# digi_5V.net
KiCad netlist of a schematic drawn in Altium Designer
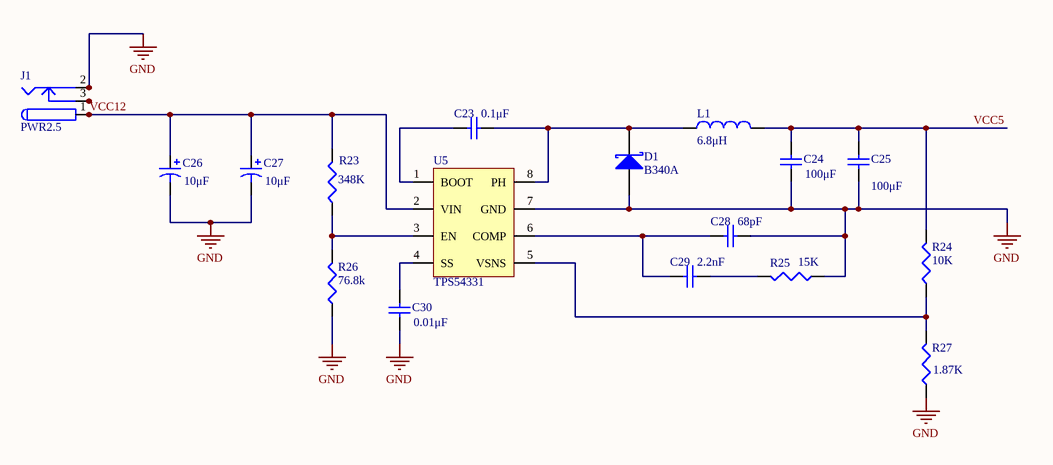
[diagram p0: digi_5V.SchDoc]

(export (version "E")
  (design (tool "Eeschema 10.0.6"))
  (components
    (comp (ref "C23")
      (value "0.1μF")
      (footprint "1608[0603]")
      (description "Capacitor (Semiconductor SIM Model)")
      (fields (field (name "Comment") "Cap Semi") (field (name "PUBLISHER") "Altium Limited"))
      (libsource (lib "Miscellaneous Devices") (part "Cap Semi"))
    )
    (comp (ref "C24")
      (value "100μF")
      (footprint "1608[0603]")
      (description "Capacitor (Semiconductor SIM Model)")
      (fields (field (name "Comment") "Cap Semi") (field (name "PUBLISHER") "Altium Limited"))
      (libsource (lib "Miscellaneous Devices") (part "Cap Semi"))
    )
    (comp (ref "C25")
      (value "100μF")
      (footprint "1608[0603]")
      (description "Capacitor (Semiconductor SIM Model)")
      (fields (field (name "Comment") "Cap Semi") (field (name "PUBLISHER") "Altium Limited"))
      (libsource (lib "Miscellaneous Devices") (part "Cap Semi"))
    )
    (comp (ref "C26")
      (value "10μF")
      (footprint "C0805")
      (description "Polarized Capacitor (Surface Mount)")
      (fields (field (name "Comment") "Cap Pol3") (field (name "PUBLISHER") "Altium Limited"))
      (libsource (lib "Miscellaneous Devices") (part "Cap Pol3"))
    )
    (comp (ref "C27")
      (value "10μF")
      (footprint "C0805")
      (description "Polarized Capacitor (Surface Mount)")
      (fields (field (name "Comment") "Cap Pol3") (field (name "PUBLISHER") "Altium Limited"))
      (libsource (lib "Miscellaneous Devices") (part "Cap Pol3"))
    )
    (comp (ref "C28")
      (value "68pF")
      (footprint "1608[0603]")
      (description "Capacitor (Semiconductor SIM Model)")
      (fields (field (name "Comment") "Cap Semi") (field (name "PUBLISHER") "Altium Limited"))
      (libsource (lib "Miscellaneous Devices") (part "Cap Semi"))
    )
    (comp (ref "C29")
      (value "2.2nF")
      (footprint "1608[0603]")
      (description "Capacitor (Semiconductor SIM Model)")
      (fields (field (name "Comment") "Cap Semi") (field (name "PUBLISHER") "Altium Limited"))
      (libsource (lib "Miscellaneous Devices") (part "Cap Semi"))
    )
    (comp (ref "C30")
      (value "0.01μF")
      (footprint "1608[0603]")
      (description "Capacitor (Semiconductor SIM Model)")
      (fields (field (name "Comment") "Cap Semi") (field (name "PUBLISHER") "Altium Limited"))
      (libsource (lib "Miscellaneous Devices") (part "Cap Semi"))
    )
    (comp (ref "D1")
      (value "B340A")
      (footprint "LED0603")
      (description "Schottky Diode")
      (fields (field (name "PUBLISHER") "Altium Limited"))
      (libsource (lib "Miscellaneous Devices") (part "D Schottky"))
    )
    (comp (ref "J1")
      (value "PWR2.5")
      (footprint "KLD-0202")
      (description "Low Voltage Power Supply Connector")
      (fields (field (name "PUBLISHER") "Altium Limited"))
      (libsource (lib "Miscellaneous Connectors") (part "PWR2.5"))
    )
    (comp (ref "L1")
      (value "6.8μH")
      (footprint "LC Inductor 127")
      (description "Inductor")
      (fields (field (name "PUBLISHER") "Altium Limited"))
      (libsource (lib "Miscellaneous Devices") (part "Inductor"))
    )
    (comp (ref "R23")
      (value "348K")
      (footprint "J1-0603")
      (description "Resistor")
      (fields (field (name "Comment") "Res3") (field (name "PUBLISHER") "Altium Limited"))
      (libsource (lib "Miscellaneous Devices") (part "Res3"))
    )
    (comp (ref "R24")
      (value "10K")
      (footprint "J1-0603")
      (description "Resistor")
      (fields (field (name "Comment") "Res3") (field (name "PUBLISHER") "Altium Limited"))
      (libsource (lib "Miscellaneous Devices") (part "Res3"))
    )
    (comp (ref "R25")
      (value "15K")
      (footprint "J1-0603")
      (description "Resistor")
      (fields (field (name "Comment") "Res3") (field (name "PUBLISHER") "Altium Limited"))
      (libsource (lib "Miscellaneous Devices") (part "Res3"))
    )
    (comp (ref "R26")
      (value "76.8k")
      (footprint "J1-0603")
      (description "Resistor")
      (fields (field (name "Comment") "Res3") (field (name "PUBLISHER") "Altium Limited"))
      (libsource (lib "Miscellaneous Devices") (part "Res3"))
    )
    (comp (ref "R27")
      (value "1.87K")
      (footprint "J1-0603")
      (description "Resistor")
      (fields (field (name "Comment") "Res3") (field (name "PUBLISHER") "Altium Limited"))
      (libsource (lib "Miscellaneous Devices") (part "Res3"))
    )
    (comp (ref "U5")
      (value "TPS54331")
      (footprint "SOIC127P600X175-8N")
      (libsource (lib "nir_usb") (part "TPS54331"))
    )
  )
  (nets
    (net (code "1") (name "/VCC5") (class "Default")
      (node (ref "C24") (pin "2") (pinfunction "2_2") (pintype "passive"))
      (node (ref "C25") (pin "2") (pinfunction "2_2") (pintype "passive"))
      (node (ref "L1") (pin "2") (pinfunction "2_2") (pintype "passive"))
      (node (ref "R24") (pin "2") (pinfunction "2_2") (pintype "passive"))
    )
    (net (code "2") (name "/VCC12") (class "Default")
      (node (ref "C26") (pin "1") (pinfunction "1_1") (pintype "passive"))
      (node (ref "C27") (pin "1") (pinfunction "1_1") (pintype "passive"))
      (node (ref "J1") (pin "1") (pinfunction "1_1") (pintype "power_in"))
      (node (ref "J1") (pin "1A") (pinfunction "1A_1A") (pintype "power_in"))
      (node (ref "J1") (pin "1B") (pinfunction "1B_1B") (pintype "power_in"))
      (node (ref "R23") (pin "2") (pinfunction "2_2") (pintype "passive"))
      (node (ref "U5") (pin "2") (pinfunction "VIN_2") (pintype "passive"))
    )
    (net (code "3") (name "GND") (class "Default")
      (node (ref "C24") (pin "1") (pinfunction "1_1") (pintype "passive"))
      (node (ref "C25") (pin "1") (pinfunction "1_1") (pintype "passive"))
      (node (ref "C26") (pin "2") (pinfunction "2_2") (pintype "passive"))
      (node (ref "C27") (pin "2") (pinfunction "2_2") (pintype "passive"))
      (node (ref "C28") (pin "1") (pinfunction "1_1") (pintype "passive"))
      (node (ref "C30") (pin "1") (pinfunction "1_1") (pintype "passive"))
      (node (ref "D1") (pin "1") (pinfunction "A_1") (pintype "passive"))
      (node (ref "J1") (pin "2") (pinfunction "2_2") (pintype "power_in"))
      (node (ref "J1") (pin "2A") (pinfunction "2A_2A") (pintype "power_in"))
      (node (ref "J1") (pin "2B") (pinfunction "2B_2B") (pintype "power_in"))
      (node (ref "R25") (pin "1") (pinfunction "1_1") (pintype "passive"))
      (node (ref "R26") (pin "1") (pinfunction "1_1") (pintype "passive"))
      (node (ref "R27") (pin "1") (pinfunction "1_1") (pintype "passive"))
      (node (ref "U5") (pin "7") (pinfunction "GND_7") (pintype "passive"))
    )
    (net (code "4") (name "Net-(C29-Pad2)") (class "Default")
      (node (ref "C29") (pin "2") (pinfunction "2_2") (pintype "passive"))
      (node (ref "R25") (pin "2") (pinfunction "2_2") (pintype "passive"))
    )
    (net (code "5") (name "Net-(D1-K)") (class "Default")
      (node (ref "C23") (pin "2") (pinfunction "2_2") (pintype "passive"))
      (node (ref "D1") (pin "2") (pinfunction "K_2") (pintype "passive"))
      (node (ref "L1") (pin "1") (pinfunction "1_1") (pintype "passive"))
      (node (ref "U5") (pin "8") (pinfunction "PH_8") (pintype "passive"))
    )
    (net (code "6") (name "Net-(J1-Pad3)") (class "Default")
      (node (ref "J1") (pin "3") (pinfunction "3_3") (pintype "power_in"))
      (node (ref "J1") (pin "3A") (pinfunction "3A_3A") (pintype "power_in"))
      (node (ref "J1") (pin "3B") (pinfunction "3B_3B") (pintype "power_in"))
    )
    (net (code "7") (name "Net-(U5-BOOT)") (class "Default")
      (node (ref "C23") (pin "1") (pinfunction "1_1") (pintype "passive"))
      (node (ref "U5") (pin "1") (pinfunction "BOOT_1") (pintype "passive"))
    )
    (net (code "8") (name "Net-(U5-COMP)") (class "Default")
      (node (ref "C28") (pin "2") (pinfunction "2_2") (pintype "passive"))
      (node (ref "C29") (pin "1") (pinfunction "1_1") (pintype "passive"))
      (node (ref "U5") (pin "6") (pinfunction "COMP_6") (pintype "passive"))
    )
    (net (code "9") (name "Net-(U5-EN)") (class "Default")
      (node (ref "R23") (pin "1") (pinfunction "1_1") (pintype "passive"))
      (node (ref "R26") (pin "2") (pinfunction "2_2") (pintype "passive"))
      (node (ref "U5") (pin "3") (pinfunction "EN_3") (pintype "passive"))
    )
    (net (code "10") (name "Net-(U5-SS)") (class "Default")
      (node (ref "C30") (pin "2") (pinfunction "2_2") (pintype "passive"))
      (node (ref "U5") (pin "4") (pinfunction "SS_4") (pintype "passive"))
    )
    (net (code "11") (name "Net-(U5-VSNS)") (class "Default")
      (node (ref "R24") (pin "1") (pinfunction "1_1") (pintype "passive"))
      (node (ref "R27") (pin "2") (pinfunction "2_2") (pintype "passive"))
      (node (ref "U5") (pin "5") (pinfunction "VSNS_5") (pintype "passive"))
    )
  )
)
